# Sheet1.net
KiCad netlist of a schematic drawn in Altium Designer
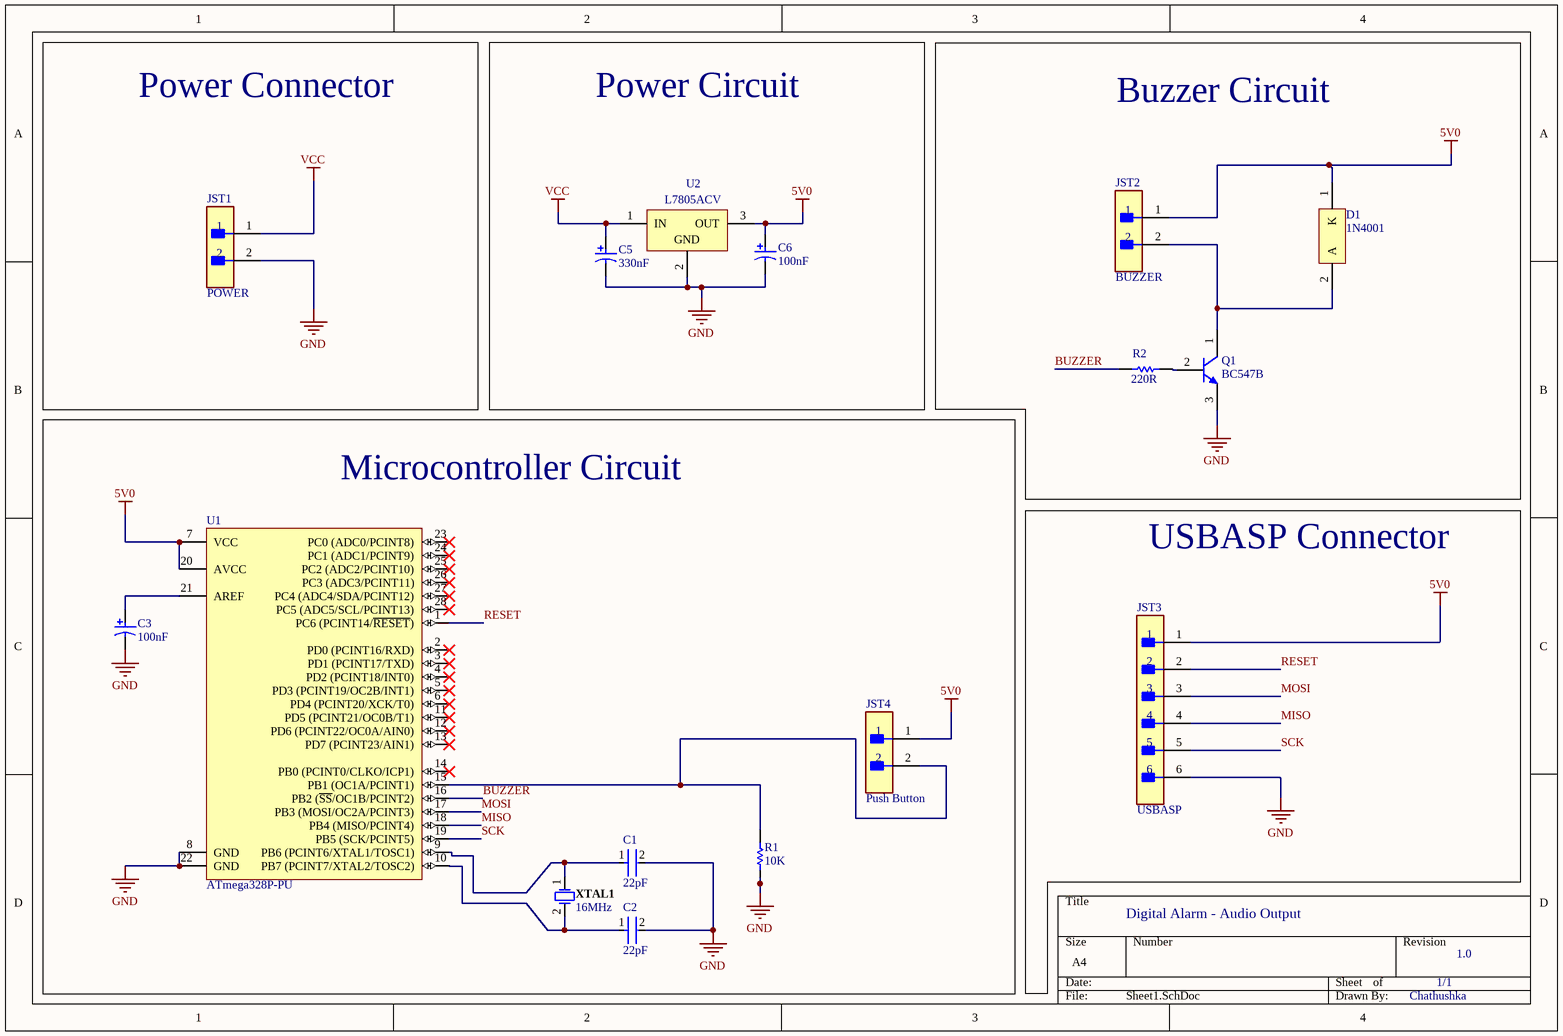
[diagram p0: Sheet1.SchDoc]

(export (version "E")
  (design (tool "Eeschema 10.0.6"))
  (components
    (comp (ref "C1")
      (value "22pF")
      (footprint "FP-RCE0K1-MFG")
      (description "Cap Ceramic 22pF 50V C0G ±5% Radial 5mm +125°C Automotive Bulk")
      (fields (field (name "TOLERANCE") "5%"))
      (libsource (lib "Altium Content Vault") (part "b4654b650e69147ec39a6b967a45e02"))
    )
    (comp (ref "C2")
      (value "22pF")
      (footprint "FP-RCE0K1-MFG")
      (description "Cap Ceramic 22pF 50V C0G ±5% Radial 5mm +125°C Automotive Bulk")
      (fields (field (name "TOLERANCE") "5%"))
      (libsource (lib "Altium Content Vault") (part "b4654b650e69147ec39a6b967a45e02"))
    )
    (comp (ref "C3")
      (value "100nF")
      (footprint "CAPPR65-350-1150X800X1250")
      (description "Aluminum Electrolytic Capacitor, 100 uF, +/- 20%, 50 V, -40 to 85 degC, 2-Pin THD, RoHS, Bulk")
      (fields (field (name "MANUFACTURER") "Panasonic") (field (name "VOLTAGE") "50V"))
      (libsource (lib "Altium Content Vault") (part "CAP-P-2"))
    )
    (comp (ref "C5")
      (value "330nF")
      (footprint "CAPPR65-350-1150X800X1250")
      (description "Aluminum Electrolytic Capacitor, 100 nF, +/- 20%, 50 V, -40 to 85 degC, 2-Pin THD, RoHS, Bulk")
      (fields (field (name "MANUFACTURER") "Panasonic") (field (name "VOLTAGE") "50V"))
      (libsource (lib "Altium Content Vault") (part "CAP-P-2"))
    )
    (comp (ref "C6")
      (value "100nF")
      (footprint "CAPPR65-350-1150X800X1250")
      (description "Aluminum Electrolytic Capacitor, 100 nF, +/- 20%, 50 V, -40 to 85 degC, 2-Pin THD, RoHS, Bulk")
      (fields (field (name "MANUFACTURER") "Panasonic") (field (name "VOLTAGE") "50V"))
      (libsource (lib "Altium Content Vault") (part "CAP-P-2"))
    )
    (comp (ref "D1")
      (value "1N4001")
      (footprint "ONSC-AXIAL_LEAD-2-59-10_P")
      (description "Standard Recovery Rectifier, 2-Pin Axial_Lead, Pb-Free, Bulk Bag")
      (fields (field (name "MANUFACTURER") "On Semiconductor"))
      (libsource (lib "Altium Content Vault") (part "ONSC-D-K1A2-2_A"))
    )
    (comp (ref "JST1")
      (value "POWER")
      (footprint "FP-B2B-XH-A_LF_SN-MFG")
      (description "CONN HEADER VERT 2POS 2.5MM")
      (libsource (lib "Altium Content Vault") (part "3bc925449376181038e59eaffc5286c"))
    )
    (comp (ref "JST2")
      (value "BUZZER")
      (footprint "FP-B2B-XH-A_LF_SN-MFG")
      (description "CONN HEADER VERT 2POS 2.5MM")
      (libsource (lib "Altium Content Vault") (part "3bc925449376181038e59eaffc5286c"))
    )
    (comp (ref "JST3")
      (value "USBASP")
      (footprint "FP-M30-6100646-MFG")
      (description "CONN HEADER VERT 6POS 1.25MM")
      (fields (field (name "MANUFACTURER PART NUMBER") "M30-6100646") (field (name "MANUFACTURER") "Harwin"))
      (libsource (lib "Altium Content Vault") (part "f2cb566baf1c37ab5a3b8e90bbeafd6"))
    )
    (comp (ref "JST4")
      (value "Push Button")
      (footprint "FP-B2B-XH-A_LF_SN-MFG")
      (description "CONN HEADER VERT 2POS 2.5MM")
      (libsource (lib "Altium Content Vault") (part "3bc925449376181038e59eaffc5286c"))
    )
    (comp (ref "Q1")
      (value "BC547B")
      (footprint "ONSC-TO-92-3-29-11")
      (description "Amplifier Transistor, NPN Silicon, 3-Pin TO-92, Bulk Box")
      (fields (field (name "MANUFACTURER") "On Semiconductor"))
      (libsource (lib "Altium Content Vault") (part "ONSC-NPN-C1B2E3-3"))
    )
    (comp (ref "R1")
      (value "10K")
      (footprint "OMTE-RES7X2.5-2")
      (fields
        (field (name "TOLERANCE") "±5%")
        (field (name "PARTNUMBER") "OD103JE")
        (field (name "MANUFACTURER") "Ohmite")
      )
      (libsource (lib "Altium Content Vault") (part "RES-2"))
    )
    (comp (ref "R2")
      (value "220R")
      (footprint "OMTE-RES7X2.5-2")
      (fields
        (field (name "TOLERANCE") "±5%")
        (field (name "PARTNUMBER") "OD103JE")
        (field (name "MANUFACTURER") "Ohmite")
      )
      (libsource (lib "Altium Content Vault") (part "RES-2"))
    )
    (comp (ref "U1")
      (value "ATmega328P-PU")
      (footprint "28P3")
      (libsource (lib "Altium Content Vault") (part "MC-8B-ATM48-IL28"))
    )
    (comp (ref "U2")
      (value "L7805ACV")
      (footprint "TO220")
      (description "Positive Voltage Regulator, 5V, 3-Pin TO-220")
      (libsource (lib "Altium Content Vault") (part "PM-REG-L4940-SIL3"))
    )
    (comp (ref "XTAL1")
      (value "16MHz")
      (footprint "FOX-FOXSLF160-20")
      (description "Resistance Weld Thru-Hole Crystal, 16 MHz, -20 to 70 degC, 2-Pin THD, RoHS, Bulk")
      (fields (field (name "TOLERANCE") "1%"))
      (libsource (lib "Altium Content Vault") (part "XTAL-1-2-2"))
    )
  )
  (nets
    (net (code "1") (name "/BUZZER") (class "Default")
      (node (ref "R2") (pin "1") (pinfunction "1_1") (pintype "passive"))
      (node (ref "U1") (pin "16") (pinfunction "PB2_(~{SS}/OC1B/PCINT2)_16") (pintype "bidirectional"))
    )
    (net (code "2") (name "/MISO") (class "Default")
      (node (ref "JST3") (pin "4") (pinfunction "4_4") (pintype "passive"))
      (node (ref "U1") (pin "18") (pinfunction "PB4_(MISO/PCINT4)_18") (pintype "bidirectional"))
    )
    (net (code "3") (name "/MOSI") (class "Default")
      (node (ref "JST3") (pin "3") (pinfunction "3_3") (pintype "passive"))
      (node (ref "U1") (pin "17") (pinfunction "PB3_(MOSI/OC2A/PCINT3)_17") (pintype "bidirectional"))
    )
    (net (code "4") (name "/RESET") (class "Default")
      (node (ref "JST3") (pin "2") (pinfunction "2_2") (pintype "passive"))
      (node (ref "U1") (pin "1") (pinfunction "PC6_(PCINT14/~{RESET})_1") (pintype "bidirectional"))
    )
    (net (code "5") (name "/SCK") (class "Default")
      (node (ref "JST3") (pin "5") (pinfunction "5_5") (pintype "passive"))
      (node (ref "U1") (pin "19") (pinfunction "PB5_(SCK/PCINT5)_19") (pintype "bidirectional"))
    )
    (net (code "6") (name "5V0") (class "Default")
      (node (ref "C6") (pin "1") (pinfunction "1_1") (pintype "passive"))
      (node (ref "D1") (pin "1") (pinfunction "K_1") (pintype "passive"))
      (node (ref "JST2") (pin "1") (pinfunction "1_1") (pintype "passive"))
      (node (ref "JST3") (pin "1") (pinfunction "1_1") (pintype "passive"))
      (node (ref "JST4") (pin "1") (pinfunction "1_1") (pintype "passive"))
      (node (ref "U1") (pin "20") (pinfunction "AVCC_20") (pintype "power_in"))
      (node (ref "U1") (pin "7") (pinfunction "VCC_7") (pintype "power_in"))
      (node (ref "U2") (pin "3") (pinfunction "OUT_3") (pintype "power_in"))
    )
    (net (code "7") (name "GND") (class "Default")
      (node (ref "C1") (pin "2") (pinfunction "2_2") (pintype "passive"))
      (node (ref "C2") (pin "2") (pinfunction "2_2") (pintype "passive"))
      (node (ref "C3") (pin "2") (pinfunction "2_2") (pintype "passive"))
      (node (ref "C5") (pin "2") (pinfunction "2_2") (pintype "passive"))
      (node (ref "C6") (pin "2") (pinfunction "2_2") (pintype "passive"))
      (node (ref "JST1") (pin "2") (pinfunction "2_2") (pintype "passive"))
      (node (ref "JST3") (pin "6") (pinfunction "6_6") (pintype "passive"))
      (node (ref "Q1") (pin "3") (pinfunction "E_3") (pintype "passive"))
      (node (ref "R1") (pin "2") (pinfunction "2_2") (pintype "passive"))
      (node (ref "U1") (pin "22") (pinfunction "GND_22") (pintype "power_in"))
      (node (ref "U1") (pin "8") (pinfunction "GND_8") (pintype "power_in"))
      (node (ref "U2") (pin "2") (pinfunction "GND_2") (pintype "power_in"))
    )
    (net (code "8") (name "Net-(D1-A)") (class "Default")
      (node (ref "D1") (pin "2") (pinfunction "A_2") (pintype "passive"))
      (node (ref "JST2") (pin "2") (pinfunction "2_2") (pintype "passive"))
      (node (ref "Q1") (pin "1") (pinfunction "C_1") (pintype "passive"))
    )
    (net (code "9") (name "Net-(Q1-B)") (class "Default")
      (node (ref "Q1") (pin "2") (pinfunction "B_2") (pintype "passive"))
      (node (ref "R2") (pin "2") (pinfunction "2_2") (pintype "passive"))
    )
    (net (code "10") (name "Net-(U1-AREF)") (class "Default")
      (node (ref "C3") (pin "1") (pinfunction "1_1") (pintype "passive"))
      (node (ref "U1") (pin "21") (pinfunction "AREF_21") (pintype "power_in"))
    )
    (net (code "11") (name "Net-(U1-PB1_(OC1A{slash}PCINT1))") (class "Default")
      (node (ref "JST4") (pin "2") (pinfunction "2_2") (pintype "passive"))
      (node (ref "R1") (pin "1") (pinfunction "1_1") (pintype "passive"))
      (node (ref "U1") (pin "15") (pinfunction "PB1_(OC1A/PCINT1)_15") (pintype "bidirectional"))
    )
    (net (code "12") (name "Net-(U1-PB6_(PCINT6{slash}XTAL1{slash}TOSC1))") (class "Default")
      (node (ref "C1") (pin "1") (pinfunction "1_1") (pintype "passive"))
      (node (ref "U1") (pin "9") (pinfunction "PB6_(PCINT6/XTAL1/TOSC1)_9") (pintype "bidirectional"))
      (node (ref "XTAL1") (pin "1") (pinfunction "1_1") (pintype "passive"))
    )
    (net (code "13") (name "Net-(U1-PB7_(PCINT7{slash}XTAL2{slash}TOSC2))") (class "Default")
      (node (ref "C2") (pin "1") (pinfunction "1_1") (pintype "passive"))
      (node (ref "U1") (pin "10") (pinfunction "PB7_(PCINT7/XTAL2/TOSC2)_10") (pintype "bidirectional"))
      (node (ref "XTAL1") (pin "2") (pinfunction "2_2") (pintype "passive"))
    )
    (net (code "14") (name "VCC") (class "Default")
      (node (ref "C5") (pin "1") (pinfunction "1_1") (pintype "passive"))
      (node (ref "JST1") (pin "1") (pinfunction "1_1") (pintype "passive"))
      (node (ref "U2") (pin "1") (pinfunction "IN_1") (pintype "power_in"))
    )
    (net (code "15") (name "unconnected-(U1-PB0_(PCINT0{slash}CLKO{slash}ICP1)-Pad14)") (class "Default")
      (node (ref "U1") (pin "14") (pinfunction "PB0_(PCINT0/CLKO/ICP1)_14") (pintype "bidirectional+no_connect"))
    )
    (net (code "16") (name "unconnected-(U1-PC0_(ADC0{slash}PCINT8)-Pad23)") (class "Default")
      (node (ref "U1") (pin "23") (pinfunction "PC0_(ADC0/PCINT8)_23") (pintype "bidirectional+no_connect"))
    )
    (net (code "17") (name "unconnected-(U1-PC1_(ADC1{slash}PCINT9)-Pad24)") (class "Default")
      (node (ref "U1") (pin "24") (pinfunction "PC1_(ADC1/PCINT9)_24") (pintype "bidirectional+no_connect"))
    )
    (net (code "18") (name "unconnected-(U1-PC2_(ADC2{slash}PCINT10)-Pad25)") (class "Default")
      (node (ref "U1") (pin "25") (pinfunction "PC2_(ADC2/PCINT10)_25") (pintype "bidirectional+no_connect"))
    )
    (net (code "19") (name "unconnected-(U1-PC3_(ADC3{slash}PCINT11)-Pad26)") (class "Default")
      (node (ref "U1") (pin "26") (pinfunction "PC3_(ADC3/PCINT11)_26") (pintype "bidirectional+no_connect"))
    )
    (net (code "20") (name "unconnected-(U1-PC4_(ADC4{slash}SDA{slash}PCINT12)-Pad27)") (class "Default")
      (node (ref "U1") (pin "27") (pinfunction "PC4_(ADC4/SDA/PCINT12)_27") (pintype "bidirectional+no_connect"))
    )
    (net (code "21") (name "unconnected-(U1-PC5_(ADC5{slash}SCL{slash}PCINT13)-Pad28)") (class "Default")
      (node (ref "U1") (pin "28") (pinfunction "PC5_(ADC5/SCL/PCINT13)_28") (pintype "bidirectional+no_connect"))
    )
    (net (code "22") (name "unconnected-(U1-PD0_(PCINT16{slash}RXD)-Pad2)") (class "Default")
      (node (ref "U1") (pin "2") (pinfunction "PD0_(PCINT16/RXD)_2") (pintype "bidirectional+no_connect"))
    )
    (net (code "23") (name "unconnected-(U1-PD1_(PCINT17{slash}TXD)-Pad3)") (class "Default")
      (node (ref "U1") (pin "3") (pinfunction "PD1_(PCINT17/TXD)_3") (pintype "bidirectional+no_connect"))
    )
    (net (code "24") (name "unconnected-(U1-PD2_(PCINT18{slash}INT0)-Pad4)") (class "Default")
      (node (ref "U1") (pin "4") (pinfunction "PD2_(PCINT18/INT0)_4") (pintype "bidirectional+no_connect"))
    )
    (net (code "25") (name "unconnected-(U1-PD3_(PCINT19{slash}OC2B{slash}INT1)-Pad5)") (class "Default")
      (node (ref "U1") (pin "5") (pinfunction "PD3_(PCINT19/OC2B/INT1)_5") (pintype "bidirectional+no_connect"))
    )
    (net (code "26") (name "unconnected-(U1-PD4_(PCINT20{slash}XCK{slash}T0)-Pad6)") (class "Default")
      (node (ref "U1") (pin "6") (pinfunction "PD4_(PCINT20/XCK/T0)_6") (pintype "bidirectional+no_connect"))
    )
    (net (code "27") (name "unconnected-(U1-PD5_(PCINT21{slash}OC0B{slash}T1)-Pad11)") (class "Default")
      (node (ref "U1") (pin "11") (pinfunction "PD5_(PCINT21/OC0B/T1)_11") (pintype "bidirectional+no_connect"))
    )
    (net (code "28") (name "unconnected-(U1-PD6_(PCINT22{slash}OC0A{slash}AIN0)-Pad12)") (class "Default")
      (node (ref "U1") (pin "12") (pinfunction "PD6_(PCINT22/OC0A/AIN0)_12") (pintype "bidirectional+no_connect"))
    )
    (net (code "29") (name "unconnected-(U1-PD7_(PCINT23{slash}AIN1)-Pad13)") (class "Default")
      (node (ref "U1") (pin "13") (pinfunction "PD7_(PCINT23/AIN1)_13") (pintype "bidirectional+no_connect"))
    )
  )
)
